# powerblade_3v1.net
KiCad netlist of a schematic drawn in EAGLE
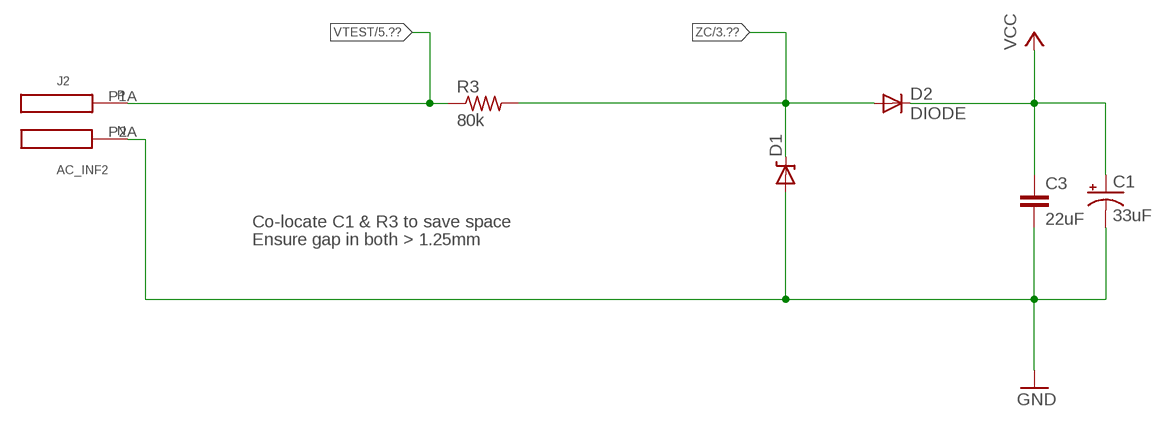
[diagram p0: schematic, sheet 1]
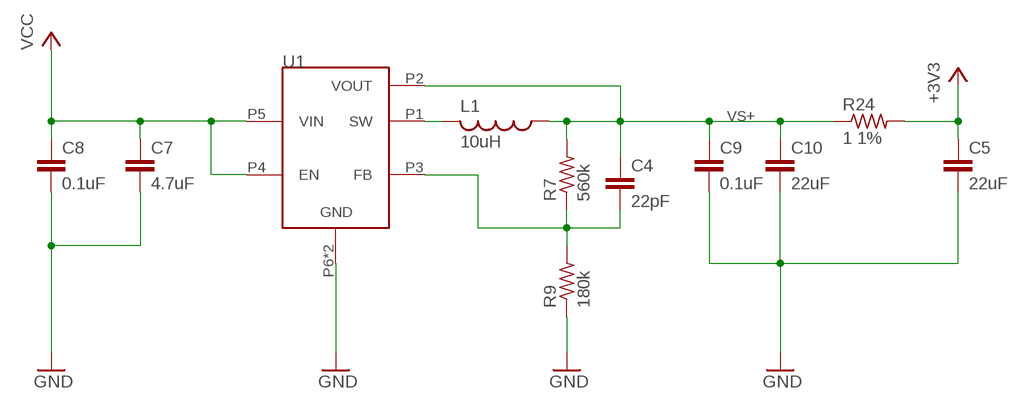
[diagram p1: schematic, sheet 2]
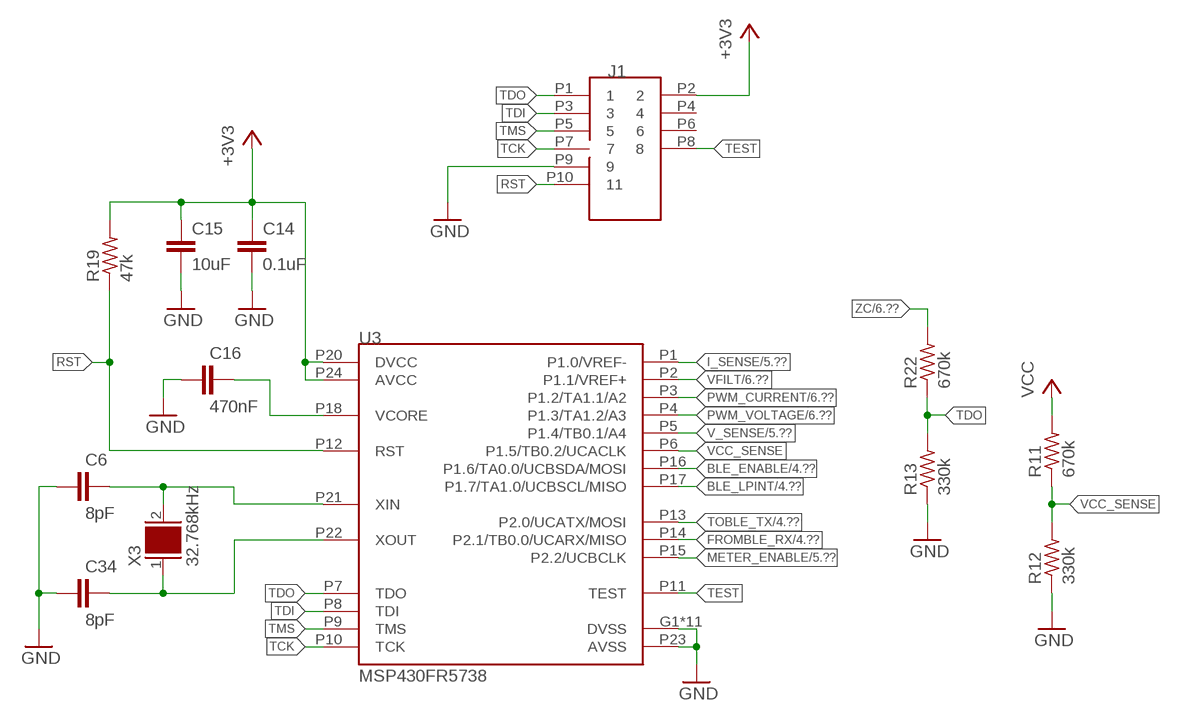
[diagram p2: schematic, sheet 3]
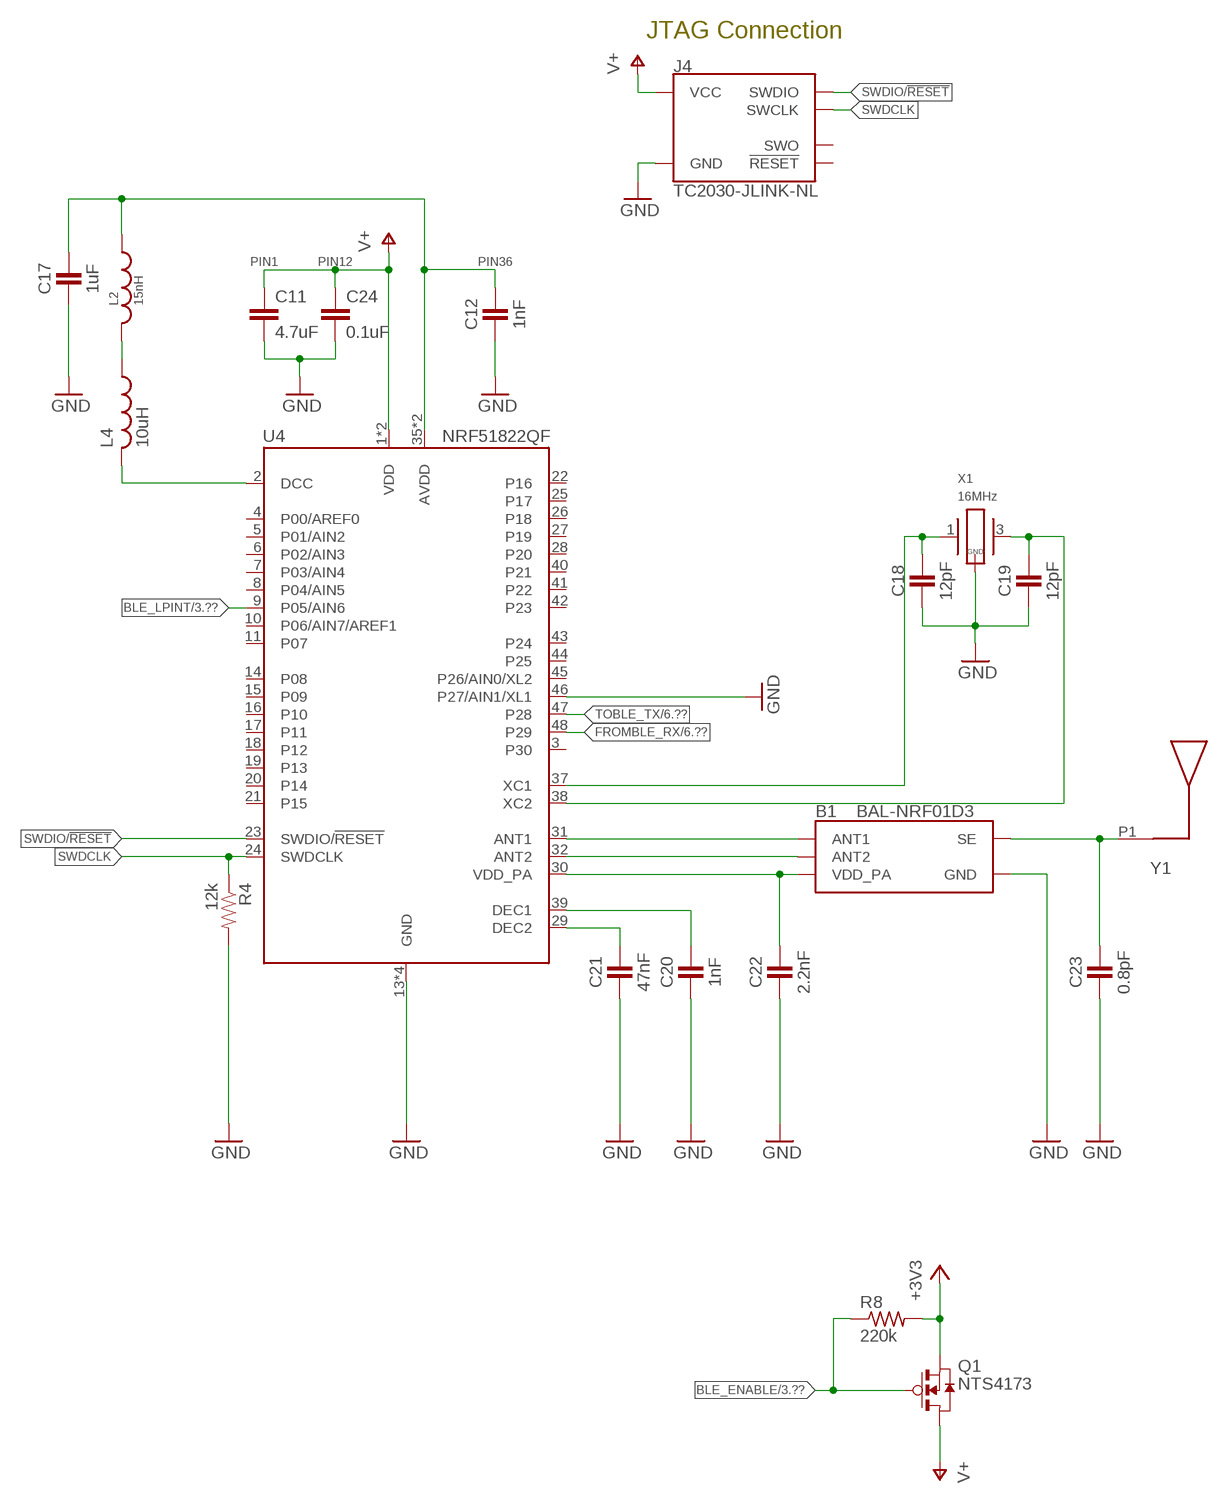
[diagram p3: schematic, sheet 4]
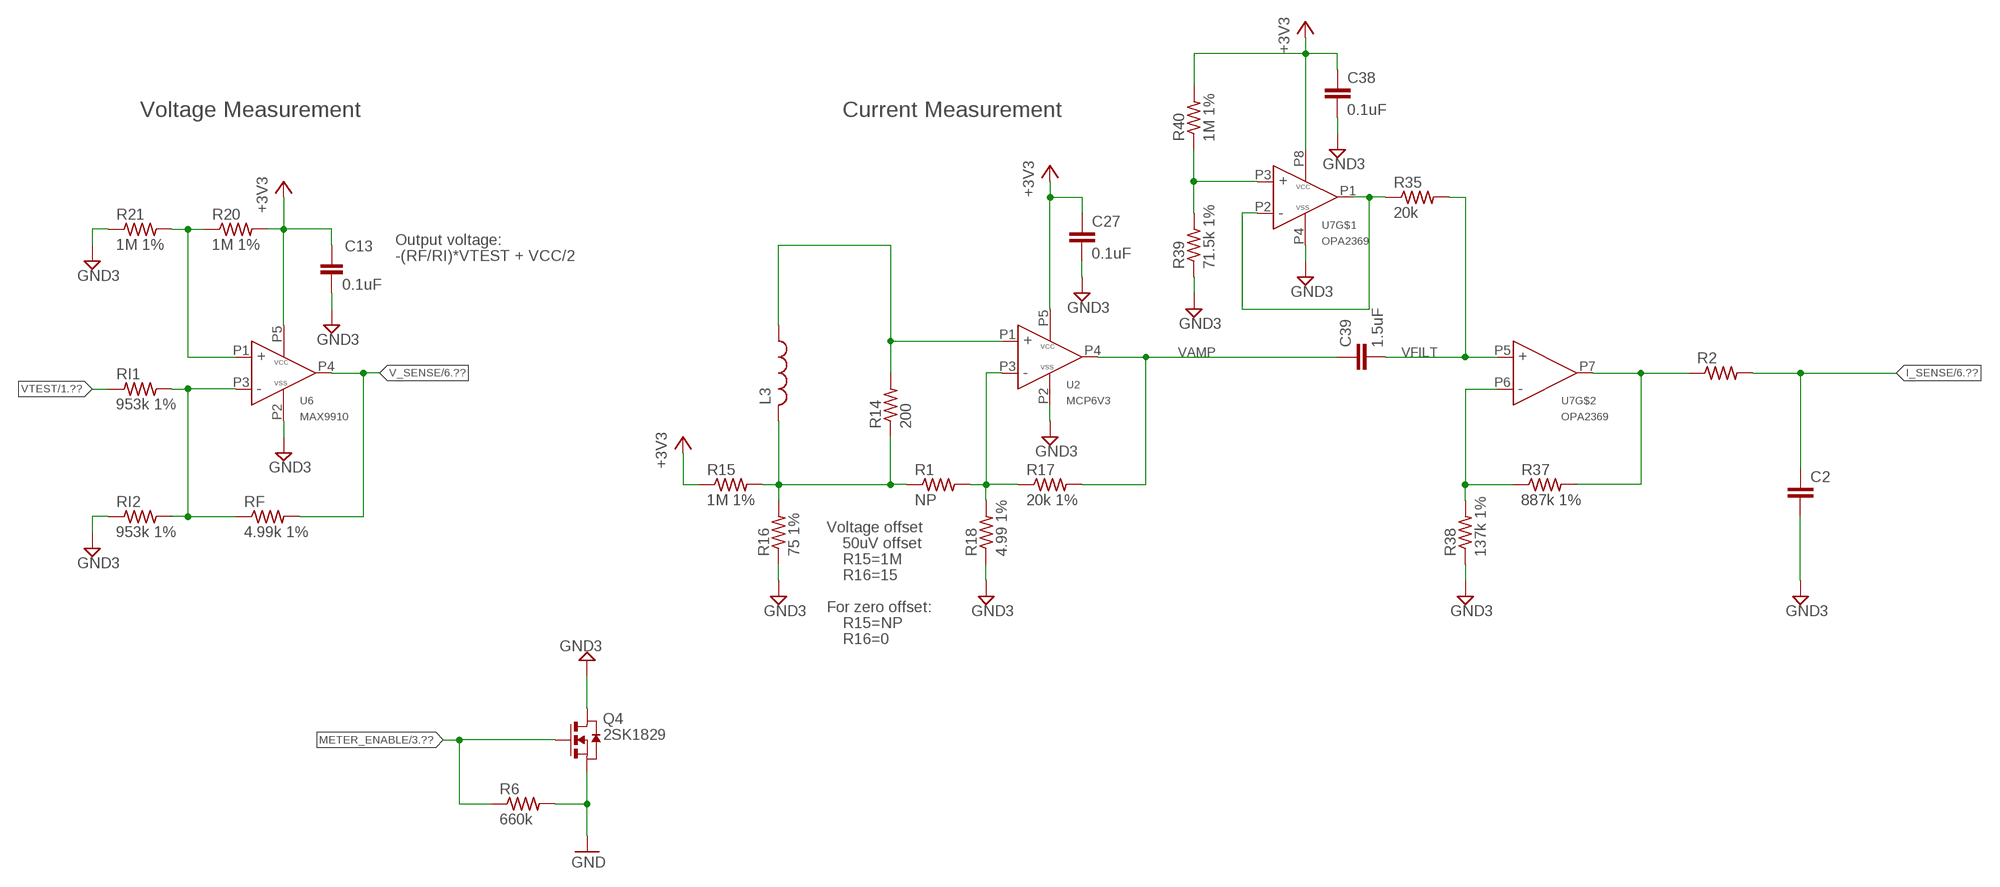
[diagram p4: schematic, sheet 5]
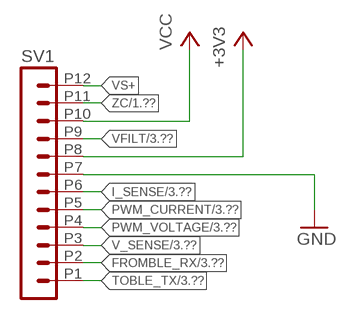
[diagram p5: schematic, sheet 6]

(export (version "E")
  (design (tool "Eeschema 10.0.6"))
  (components
    (comp (ref "C2")
      (value "C-EUC0402_SM")
      (footprint "eagle-import:C0402_SM")
      (libsource (lib "eagle-import") (part "C-EUC0402_SM"))
    )
    (comp (ref "C13")
      (value "0.1uF")
      (footprint "eagle-import:0402_CAP")
      (libsource (lib "eagle-import") (part "CAPACITOR"))
    )
    (comp (ref "C27")
      (value "0.1uF")
      (footprint "eagle-import:C0402_SM")
      (libsource (lib "eagle-import") (part "C-EUC0402_SM"))
    )
    (comp (ref "C38")
      (value "0.1uF")
      (footprint "eagle-import:C0402_SM")
      (libsource (lib "eagle-import") (part "C-EUC0402_SM"))
    )
    (comp (ref "C39")
      (value "1.5uF")
      (footprint "eagle-import:C0402_SM")
      (libsource (lib "eagle-import") (part "C-EUC0402_SM"))
    )
    (comp (ref "L3")
      (value "L-USL0805")
      (footprint "eagle-import:L0805")
      (libsource (lib "eagle-import") (part "L-USL0805"))
    )
    (comp (ref "Q4")
      (value "2SK1829")
      (footprint "eagle-import:SC-70-3")
      (libsource (lib "eagle-import") (part "2SK1829"))
    )
    (comp (ref "R1")
      (value "NP")
      (footprint "eagle-import:R0402_SM")
      (libsource (lib "eagle-import") (part "R-US_R0402_SM"))
    )
    (comp (ref "R2")
      (value "R-US_R0402_SM")
      (footprint "eagle-import:R0402_SM")
      (libsource (lib "eagle-import") (part "R-US_R0402_SM"))
    )
    (comp (ref "R6")
      (value "660k")
      (footprint "eagle-import:R0402_SM")
      (libsource (lib "eagle-import") (part "R-US_R0402_SM"))
    )
    (comp (ref "R14")
      (value "200")
      (footprint "eagle-import:R0402_SM")
      (libsource (lib "eagle-import") (part "R-US_R0402_SM"))
    )
    (comp (ref "R15")
      (value "1M 1%")
      (footprint "eagle-import:R0402_SM")
      (libsource (lib "eagle-import") (part "R-US_R0402_SM"))
    )
    (comp (ref "R16")
      (value "75 1%")
      (footprint "eagle-import:R0402_SM")
      (libsource (lib "eagle-import") (part "R-US_R0402_SM"))
    )
    (comp (ref "R17")
      (value "20k 1%")
      (footprint "eagle-import:R0402_SM")
      (libsource (lib "eagle-import") (part "R-US_R0402_SM"))
    )
    (comp (ref "R18")
      (value "4.99 1%")
      (footprint "eagle-import:R0402_SM")
      (libsource (lib "eagle-import") (part "R-US_R0402_SM"))
    )
    (comp (ref "R20")
      (value "1M 1%")
      (footprint "eagle-import:R0402_SM")
      (libsource (lib "eagle-import") (part "R-US_R0402_SM"))
    )
    (comp (ref "R21")
      (value "1M 1%")
      (footprint "eagle-import:R0402_SM")
      (libsource (lib "eagle-import") (part "R-US_R0402_SM"))
    )
    (comp (ref "R35")
      (value "20k")
      (footprint "eagle-import:R0402_SM")
      (libsource (lib "eagle-import") (part "R-US_R0402_SM"))
    )
    (comp (ref "R37")
      (value "887k 1%")
      (footprint "eagle-import:R0402_SM")
      (libsource (lib "eagle-import") (part "R-US_R0402_SM"))
    )
    (comp (ref "R38")
      (value "137k 1%")
      (footprint "eagle-import:R0402_SM")
      (libsource (lib "eagle-import") (part "R-US_R0402_SM"))
    )
    (comp (ref "R39")
      (value "71.5k 1%")
      (footprint "eagle-import:R0402_SM")
      (libsource (lib "eagle-import") (part "R-US_R0402_SM"))
    )
    (comp (ref "R40")
      (value "1M 1%")
      (footprint "eagle-import:R0402_SM")
      (libsource (lib "eagle-import") (part "R-US_R0402_SM"))
    )
    (comp (ref "RF")
      (value "4.99k 1%")
      (footprint "eagle-import:R0402_SM")
      (libsource (lib "eagle-import") (part "R-US_R0402_SM"))
    )
    (comp (ref "RI1")
      (value "953k 1%")
      (footprint "eagle-import:R0402_SM")
      (libsource (lib "eagle-import") (part "R-US_R0402_SM"))
    )
    (comp (ref "RI2")
      (value "953k 1%")
      (footprint "eagle-import:R0402_SM")
      (libsource (lib "eagle-import") (part "R-US_R0402_SM"))
    )
    (comp (ref "U2")
      (value "MCP6V3")
      (footprint "eagle-import:SC70-5")
      (libsource (lib "eagle-import") (part "MCP6V3"))
    )
    (comp (ref "U6")
      (value "MAX9910")
      (footprint "eagle-import:SC70-5")
      (fields (field (name "DIGIKEY") "296-25252-1-ND"))
      (libsource (lib "eagle-import") (part "MAX9910"))
    )
    (comp (ref "U7")
      (value "OPA2369")
      (footprint "eagle-import:SOT-23-8")
      (libsource (lib "eagle-import") (part "OPA2369"))
    )
    (comp (ref "C6")
      (value "8pF")
      (footprint "eagle-import:C0402_SM")
      (libsource (lib "eagle-import") (part "C-EUC0402_SM"))
    )
    (comp (ref "C14")
      (value "0.1uF")
      (footprint "eagle-import:C0402_SM")
      (libsource (lib "eagle-import") (part "C-EUC0402_SM"))
    )
    (comp (ref "C15")
      (value "10uF")
      (footprint "eagle-import:C0603_SM")
      (libsource (lib "eagle-import") (part "C-EUC0603_SM"))
    )
    (comp (ref "C16")
      (value "470nF")
      (footprint "eagle-import:C0402_SM")
      (libsource (lib "eagle-import") (part "C-EUC0402_SM"))
    )
    (comp (ref "C34")
      (value "8pF")
      (footprint "eagle-import:C0402_SM")
      (libsource (lib "eagle-import") (part "C-EUC0402_SM"))
    )
    (comp (ref "J1")
      (value "JTAG_14PIN_IDC-ND")
      (footprint "eagle-import:TC2050-IDC-NL-430-ND")
      (libsource (lib "eagle-import") (part "JTAG_14PIN_IDC-ND"))
    )
    (comp (ref "R11")
      (value "670k")
      (footprint "eagle-import:R0402_SM")
      (libsource (lib "eagle-import") (part "R-US_R0402_SM"))
    )
    (comp (ref "R12")
      (value "330k")
      (footprint "eagle-import:R0402_SM")
      (libsource (lib "eagle-import") (part "R-US_R0402_SM"))
    )
    (comp (ref "R13")
      (value "330k")
      (footprint "eagle-import:R0402_SM")
      (libsource (lib "eagle-import") (part "R-US_R0402_SM"))
    )
    (comp (ref "R19")
      (value "47k")
      (footprint "eagle-import:R0402_SM")
      (libsource (lib "eagle-import") (part "R-US_R0402_SM"))
    )
    (comp (ref "R22")
      (value "670k")
      (footprint "eagle-import:R0402_SM")
      (libsource (lib "eagle-import") (part "R-US_R0402_SM"))
    )
    (comp (ref "U3")
      (value "MSP430FR5738")
      (footprint "eagle-import:VQFN-24")
      (libsource (lib "eagle-import") (part "MSP430FR5738"))
    )
    (comp (ref "X3")
      (value "32.768kHz")
      (footprint "eagle-import:0805")
      (libsource (lib "eagle-import") (part "CRYSTAL_0805"))
    )
    (comp (ref "C4")
      (value "22pF")
      (footprint "eagle-import:C0402_SM")
      (libsource (lib "eagle-import") (part "C-EUC0402_SM"))
    )
    (comp (ref "C5")
      (value "22uF")
      (footprint "eagle-import:C0603_TN")
      (libsource (lib "eagle-import") (part "C-EUC0603_TN"))
    )
    (comp (ref "C7")
      (value "4.7uF")
      (footprint "eagle-import:C0402_SM")
      (libsource (lib "eagle-import") (part "C-EUC0402_SM"))
    )
    (comp (ref "C8")
      (value "0.1uF")
      (footprint "eagle-import:C0402_SM")
      (libsource (lib "eagle-import") (part "C-EUC0402_SM"))
    )
    (comp (ref "C9")
      (value "0.1uF")
      (footprint "eagle-import:C0402_SM")
      (libsource (lib "eagle-import") (part "C-EUC0402_SM"))
    )
    (comp (ref "C10")
      (value "22uF")
      (footprint "eagle-import:C0603_SM")
      (libsource (lib "eagle-import") (part "C-EUC0603_SM"))
    )
    (comp (ref "L1")
      (value "10uH")
      (footprint "eagle-import:L0805")
      (libsource (lib "eagle-import") (part "L-USL0805"))
    )
    (comp (ref "R7")
      (value "560k")
      (footprint "eagle-import:R0402_SM")
      (libsource (lib "eagle-import") (part "R-US_R0402_SM"))
    )
    (comp (ref "R9")
      (value "180k")
      (footprint "eagle-import:R0402_SM")
      (libsource (lib "eagle-import") (part "R-US_R0402_SM"))
    )
    (comp (ref "R24")
      (value "1 1%")
      (footprint "eagle-import:R0603_SM")
      (libsource (lib "eagle-import") (part "R-US_R0603_SM"))
    )
    (comp (ref "U1")
      (value "TPS62122")
      (footprint "eagle-import:WDFN-6")
      (libsource (lib "eagle-import") (part "TPS62122"))
    )
    (comp (ref "C1")
      (value "33uF")
      (footprint "eagle-import:CPOL0805_SM")
      (libsource (lib "eagle-import") (part "CPOL-US0805_SM"))
    )
    (comp (ref "C3")
      (value "22uF")
      (footprint "eagle-import:C0603_SM")
      (libsource (lib "eagle-import") (part "C-EUC0603_SM"))
    )
    (comp (ref "D1")
      (value "ZENERBZT52")
      (footprint "eagle-import:BZT52")
      (fields (field (name "DIGIKEY") "BZT52C10T-7DICT-ND "))
      (libsource (lib "eagle-import") (part "ZENERBZT52"))
    )
    (comp (ref "D2")
      (value "DIODE")
      (footprint "eagle-import:BAS521")
      (libsource (lib "eagle-import") (part "DIODE"))
    )
    (comp (ref "J2")
      (value "AC_INF2")
      (footprint "eagle-import:AC3_F2")
      (libsource (lib "eagle-import") (part "AC_INF2"))
    )
    (comp (ref "R3")
      (value "80k")
      (footprint "eagle-import:R1210")
      (libsource (lib "eagle-import") (part "R-US_R1210"))
    )
    (comp (ref "B1")
      (value "BAL-NRF01D3")
      (footprint "eagle-import:BAL-NRF01D3")
      (libsource (lib "eagle-import") (part "BAL-NRF01D3"))
    )
    (comp (ref "C11")
      (value "4.7uF")
      (footprint "eagle-import:C0402_SM")
      (libsource (lib "eagle-import") (part "C-EUC0402_SM"))
    )
    (comp (ref "C12")
      (value "1nF")
      (footprint "eagle-import:0402_CAP")
      (libsource (lib "eagle-import") (part "CAPACITOR"))
    )
    (comp (ref "C17")
      (value "1uF")
      (footprint "eagle-import:0402_CAP")
      (libsource (lib "eagle-import") (part "CAPACITOR"))
    )
    (comp (ref "C18")
      (value "12pF")
      (footprint "eagle-import:0402_CAP")
      (libsource (lib "eagle-import") (part "CAPACITOR"))
    )
    (comp (ref "C19")
      (value "12pF")
      (footprint "eagle-import:0402_CAP")
      (libsource (lib "eagle-import") (part "CAPACITOR"))
    )
    (comp (ref "C20")
      (value "1nF")
      (footprint "eagle-import:0402_CAP")
      (libsource (lib "eagle-import") (part "CAPACITOR"))
    )
    (comp (ref "C21")
      (value "47nF")
      (footprint "eagle-import:0402_CAP")
      (libsource (lib "eagle-import") (part "CAPACITOR"))
    )
    (comp (ref "C22")
      (value "2.2nF")
      (footprint "eagle-import:0402_CAP")
      (libsource (lib "eagle-import") (part "CAPACITOR"))
    )
    (comp (ref "C23")
      (value "0.8pF")
      (footprint "eagle-import:0402_CAP")
      (libsource (lib "eagle-import") (part "CAPACITOR"))
    )
    (comp (ref "C24")
      (value "0.1uF")
      (footprint "eagle-import:C0402_SM")
      (libsource (lib "eagle-import") (part "C-EUC0402_SM"))
    )
    (comp (ref "J4")
      (value "TC2030-JLINK-NL")
      (footprint "eagle-import:TC2030-IDC-NL")
      (libsource (lib "eagle-import") (part "TC2030-JLINK-NL"))
    )
    (comp (ref "L2")
      (value "15nH")
      (footprint "eagle-import:0402_CAP")
      (libsource (lib "eagle-import") (part "INDUCTOR0402"))
    )
    (comp (ref "L4")
      (value "10uH")
      (footprint "eagle-import:C0603_TN")
      (libsource (lib "eagle-import") (part "L-USL0603_TN"))
    )
    (comp (ref "Q1")
      (value "NTS4173")
      (footprint "eagle-import:SC-70-3")
      (libsource (lib "eagle-import") (part "NTS4173"))
    )
    (comp (ref "R4")
      (value "12k")
      (footprint "eagle-import:0402_RES")
      (libsource (lib "eagle-import") (part "RESISTOR"))
    )
    (comp (ref "R8")
      (value "220k")
      (footprint "eagle-import:R0402_SM")
      (libsource (lib "eagle-import") (part "R-US_R0402_SM"))
    )
    (comp (ref "U4")
      (value "NRF51822QF")
      (footprint "eagle-import:QFN-48-6MM")
      (libsource (lib "eagle-import") (part "NRF51822QF"))
    )
    (comp (ref "X1")
      (value "16MHz")
      (footprint "eagle-import:TXC-8Y")
      (libsource (lib "eagle-import") (part "TXC-8Y"))
    )
    (comp (ref "Y1")
      (value "UREACH_XTEND")
      (footprint "eagle-import:UREACH_XTEND")
      (libsource (lib "eagle-import") (part "UREACH_XTEND"))
    )
    (comp (ref "SV1")
      (value "MA12-11M27")
      (footprint "eagle-import:MA12-1_1MM27")
      (libsource (lib "eagle-import") (part "MA12-11M27"))
    )
  )
  (nets
    (net (code "1") (name "+3V3") (class "Default")
      (node (ref "C13") (pin "1") (pinfunction "1_1") (pintype "bidirectional"))
      (node (ref "C14") (pin "1") (pinfunction "1_1") (pintype "passive"))
      (node (ref "C15") (pin "1") (pinfunction "1_1") (pintype "passive"))
      (node (ref "C27") (pin "1") (pinfunction "1_1") (pintype "passive"))
      (node (ref "C38") (pin "1") (pinfunction "1_1") (pintype "passive"))
      (node (ref "C5") (pin "1") (pinfunction "1_1") (pintype "passive"))
      (node (ref "J1") (pin "P2") (pinfunction "2_P2") (pintype "bidirectional"))
      (node (ref "Q1") (pin "P2") (pinfunction "S_P2") (pintype "passive"))
      (node (ref "R15") (pin "1") (pinfunction "1_1") (pintype "passive"))
      (node (ref "R19") (pin "2") (pinfunction "2_2") (pintype "passive"))
      (node (ref "R20") (pin "2") (pinfunction "2_2") (pintype "passive"))
      (node (ref "R24") (pin "2") (pinfunction "2_2") (pintype "passive"))
      (node (ref "R40") (pin "2") (pinfunction "2_2") (pintype "passive"))
      (node (ref "R8") (pin "2") (pinfunction "2_2") (pintype "passive"))
      (node (ref "SV1") (pin "P8") (pinfunction "8_P8") (pintype "passive"))
      (node (ref "U2") (pin "P5") (pinfunction "VCC_P5") (pintype "bidirectional"))
      (node (ref "U3") (pin "P20") (pinfunction "DVCC_P20") (pintype "bidirectional"))
      (node (ref "U3") (pin "P24") (pinfunction "AVCC_P24") (pintype "bidirectional"))
      (node (ref "U6") (pin "P5") (pinfunction "VCC_P5") (pintype "bidirectional"))
      (node (ref "U7") (pin "P8") (pinfunction "VCC_P8") (pintype "bidirectional"))
    )
    (net (code "2") (name "BLE_ENABLE") (class "Default")
      (node (ref "Q1") (pin "P1") (pinfunction "G_P1") (pintype "passive"))
      (node (ref "R8") (pin "1") (pinfunction "1_1") (pintype "passive"))
      (node (ref "U3") (pin "P16") (pinfunction "P1.6/TA0.0/UCBSDA/MOSI_P16") (pintype "bidirectional"))
    )
    (net (code "3") (name "BLE_LPINT") (class "Default")
      (node (ref "U3") (pin "P17") (pinfunction "P1.7/TA1.0/UCBSCL/MISO_P17") (pintype "bidirectional"))
      (node (ref "U4") (pin "9") (pinfunction "P05/AIN6_9") (pintype "bidirectional"))
    )
    (net (code "4") (name "FROMBLE_RX") (class "Default")
      (node (ref "SV1") (pin "P2") (pinfunction "2_P2") (pintype "passive"))
      (node (ref "U3") (pin "P14") (pinfunction "P2.1/TB0.0/UCARX/MISO_P14") (pintype "bidirectional"))
      (node (ref "U4") (pin "48") (pinfunction "P29_48") (pintype "bidirectional"))
    )
    (net (code "5") (name "GND") (class "Default")
      (node (ref "B1") (pin "GND") (pinfunction "GND_GND") (pintype "bidirectional"))
      (node (ref "C1") (pin "-") (pinfunction "-_-") (pintype "passive"))
      (node (ref "C10") (pin "2") (pinfunction "2_2") (pintype "passive"))
      (node (ref "C11") (pin "2") (pinfunction "2_2") (pintype "passive"))
      (node (ref "C12") (pin "2") (pinfunction "2_2") (pintype "bidirectional"))
      (node (ref "C14") (pin "2") (pinfunction "2_2") (pintype "passive"))
      (node (ref "C15") (pin "2") (pinfunction "2_2") (pintype "passive"))
      (node (ref "C16") (pin "1") (pinfunction "1_1") (pintype "passive"))
      (node (ref "C17") (pin "2") (pinfunction "2_2") (pintype "bidirectional"))
      (node (ref "C18") (pin "2") (pinfunction "2_2") (pintype "bidirectional"))
      (node (ref "C19") (pin "2") (pinfunction "2_2") (pintype "bidirectional"))
      (node (ref "C20") (pin "2") (pinfunction "2_2") (pintype "bidirectional"))
      (node (ref "C21") (pin "2") (pinfunction "2_2") (pintype "bidirectional"))
      (node (ref "C22") (pin "2") (pinfunction "2_2") (pintype "bidirectional"))
      (node (ref "C23") (pin "2") (pinfunction "2_2") (pintype "bidirectional"))
      (node (ref "C24") (pin "2") (pinfunction "2_2") (pintype "passive"))
      (node (ref "C3") (pin "2") (pinfunction "2_2") (pintype "passive"))
      (node (ref "C34") (pin "1") (pinfunction "1_1") (pintype "passive"))
      (node (ref "C5") (pin "2") (pinfunction "2_2") (pintype "passive"))
      (node (ref "C6") (pin "1") (pinfunction "1_1") (pintype "passive"))
      (node (ref "C7") (pin "2") (pinfunction "2_2") (pintype "passive"))
      (node (ref "C8") (pin "2") (pinfunction "2_2") (pintype "passive"))
      (node (ref "C9") (pin "2") (pinfunction "2_2") (pintype "passive"))
      (node (ref "D1") (pin "A") (pinfunction "A_A") (pintype "passive"))
      (node (ref "J1") (pin "P9") (pinfunction "9_P9") (pintype "bidirectional"))
      (node (ref "J2") (pin "P2A") (pinfunction "N_P2A") (pintype "bidirectional"))
      (node (ref "J4") (pin "5") (pinfunction "GND_5") (pintype "bidirectional"))
      (node (ref "Q4") (pin "P2") (pinfunction "S_P2") (pintype "passive"))
      (node (ref "R12") (pin "1") (pinfunction "1_1") (pintype "passive"))
      (node (ref "R13") (pin "1") (pinfunction "1_1") (pintype "passive"))
      (node (ref "R4") (pin "2") (pinfunction "2_2") (pintype "passive"))
      (node (ref "R6") (pin "2") (pinfunction "2_2") (pintype "passive"))
      (node (ref "R9") (pin "1") (pinfunction "1_1") (pintype "passive"))
      (node (ref "SV1") (pin "P7") (pinfunction "7_P7") (pintype "passive"))
      (node (ref "U1") (pin "P6") (pinfunction "GND_P6") (pintype "bidirectional"))
      (node (ref "U1") (pin "PAD") (pinfunction "GND_PAD") (pintype "bidirectional"))
      (node (ref "U3") (pin "G1") (pinfunction "DVSS_G1") (pintype "bidirectional"))
      (node (ref "U3") (pin "G2") (pinfunction "DVSS_G2") (pintype "bidirectional"))
      (node (ref "U3") (pin "G3") (pinfunction "DVSS_G3") (pintype "bidirectional"))
      (node (ref "U3") (pin "G4") (pinfunction "DVSS_G4") (pintype "bidirectional"))
      (node (ref "U3") (pin "G5") (pinfunction "DVSS_G5") (pintype "bidirectional"))
      (node (ref "U3") (pin "G6") (pinfunction "DVSS_G6") (pintype "bidirectional"))
      (node (ref "U3") (pin "G7") (pinfunction "DVSS_G7") (pintype "bidirectional"))
      (node (ref "U3") (pin "G8") (pinfunction "DVSS_G8") (pintype "bidirectional"))
      (node (ref "U3") (pin "G9") (pinfunction "DVSS_G9") (pintype "bidirectional"))
      (node (ref "U3") (pin "P19") (pinfunction "DVSS_P19") (pintype "bidirectional"))
      (node (ref "U3") (pin "P23") (pinfunction "AVSS_P23") (pintype "bidirectional"))
      (node (ref "U3") (pin "PAD") (pinfunction "DVSS_PAD") (pintype "bidirectional"))
      (node (ref "U4") (pin "13") (pinfunction "GND_13") (pintype "bidirectional"))
      (node (ref "U4") (pin "33") (pinfunction "GND_33") (pintype "bidirectional"))
      (node (ref "U4") (pin "34") (pinfunction "GND_34") (pintype "bidirectional"))
      (node (ref "U4") (pin "46") (pinfunction "P27/AIN1/XL1_46") (pintype "bidirectional"))
      (node (ref "U4") (pin "GND") (pinfunction "GND_GND") (pintype "bidirectional"))
      (node (ref "X1") (pin "2") (pinfunction "GND_2") (pintype "bidirectional"))
      (node (ref "X1") (pin "4") (pinfunction "GND_4") (pintype "bidirectional"))
    )
    (net (code "6") (name "GND3") (class "Default")
      (node (ref "C13") (pin "2") (pinfunction "2_2") (pintype "bidirectional"))
      (node (ref "C2") (pin "2") (pinfunction "2_2") (pintype "passive"))
      (node (ref "C27") (pin "2") (pinfunction "2_2") (pintype "passive"))
      (node (ref "C38") (pin "2") (pinfunction "2_2") (pintype "passive"))
      (node (ref "Q4") (pin "P3") (pinfunction "D_P3") (pintype "passive"))
      (node (ref "R16") (pin "1") (pinfunction "1_1") (pintype "passive"))
      (node (ref "R18") (pin "1") (pinfunction "1_1") (pintype "passive"))
      (node (ref "R21") (pin "1") (pinfunction "1_1") (pintype "passive"))
      (node (ref "R38") (pin "1") (pinfunction "1_1") (pintype "passive"))
      (node (ref "R39") (pin "1") (pinfunction "1_1") (pintype "passive"))
      (node (ref "RI2") (pin "1") (pinfunction "1_1") (pintype "passive"))
      (node (ref "U2") (pin "P2") (pinfunction "VSS_P2") (pintype "bidirectional"))
      (node (ref "U6") (pin "P2") (pinfunction "VSS_P2") (pintype "bidirectional"))
      (node (ref "U7") (pin "P4") (pinfunction "VSS_P4") (pintype "bidirectional"))
    )
    (net (code "7") (name "I_SENSE") (class "Default")
      (node (ref "C2") (pin "1") (pinfunction "1_1") (pintype "passive"))
      (node (ref "R2") (pin "2") (pinfunction "2_2") (pintype "passive"))
      (node (ref "SV1") (pin "P6") (pinfunction "6_P6") (pintype "passive"))
      (node (ref "U3") (pin "P1") (pinfunction "P1.0/VREF-_P1") (pintype "bidirectional"))
    )
    (net (code "8") (name "METER_ENABLE") (class "Default")
      (node (ref "Q4") (pin "P1") (pinfunction "G_P1") (pintype "passive"))
      (node (ref "R6") (pin "1") (pinfunction "1_1") (pintype "passive"))
      (node (ref "U3") (pin "P15") (pinfunction "P2.2/UCBCLK_P15") (pintype "bidirectional"))
    )
    (net (code "9") (name "Net-(B1-PadSE)") (class "Default")
      (node (ref "B1") (pin "SE") (pinfunction "SE_SE") (pintype "bidirectional"))
      (node (ref "C23") (pin "1") (pinfunction "1_1") (pintype "bidirectional"))
      (node (ref "Y1") (pin "P1") (pinfunction "P1_P1") (pintype "bidirectional"))
    )
    (net (code "10") (name "Net-(B1-VDD_PA)") (class "Default")
      (node (ref "B1") (pin "VCC") (pinfunction "VDD_PA_VCC") (pintype "bidirectional"))
      (node (ref "C22") (pin "1") (pinfunction "1_1") (pintype "bidirectional"))
      (node (ref "U4") (pin "30") (pinfunction "VDD_PA_30") (pintype "bidirectional"))
    )
    (net (code "11") (name "Net-(C12-Pad1)") (class "Default")
      (node (ref "C12") (pin "1") (pinfunction "1_1") (pintype "bidirectional"))
      (node (ref "C17") (pin "1") (pinfunction "1_1") (pintype "bidirectional"))
      (node (ref "L2") (pin "1") (pinfunction "1_1") (pintype "bidirectional"))
      (node (ref "U4") (pin "35") (pinfunction "AVDD_35") (pintype "bidirectional"))
      (node (ref "U4") (pin "36") (pinfunction "AVDD_36") (pintype "bidirectional"))
    )
    (net (code "12") (name "Net-(L2-Pad2)") (class "Default")
      (node (ref "L2") (pin "2") (pinfunction "2_2") (pintype "bidirectional"))
      (node (ref "L4") (pin "1") (pinfunction "1_1") (pintype "passive"))
    )
    (net (code "13") (name "Net-(L3-Pad2)") (class "Default")
      (node (ref "L3") (pin "2") (pinfunction "2_2") (pintype "passive"))
      (node (ref "R1") (pin "1") (pinfunction "1_1") (pintype "passive"))
      (node (ref "R14") (pin "1") (pinfunction "1_1") (pintype "passive"))
      (node (ref "R15") (pin "2") (pinfunction "2_2") (pintype "passive"))
      (node (ref "R16") (pin "2") (pinfunction "2_2") (pintype "passive"))
    )
    (net (code "14") (name "Net-(U1-FB)") (class "Default")
      (node (ref "C4") (pin "2") (pinfunction "2_2") (pintype "passive"))
      (node (ref "R7") (pin "1") (pinfunction "1_1") (pintype "passive"))
      (node (ref "R9") (pin "2") (pinfunction "2_2") (pintype "passive"))
      (node (ref "U1") (pin "P3") (pinfunction "FB_P3") (pintype "bidirectional"))
    )
    (net (code "15") (name "Net-(U1-SW)") (class "Default")
      (node (ref "L1") (pin "2") (pinfunction "2_2") (pintype "passive"))
      (node (ref "U1") (pin "P1") (pinfunction "SW_P1") (pintype "bidirectional"))
    )
    (net (code "16") (name "Net-(U2-IN+)") (class "Default")
      (node (ref "L3") (pin "1") (pinfunction "1_1") (pintype "passive"))
      (node (ref "R14") (pin "2") (pinfunction "2_2") (pintype "passive"))
      (node (ref "U2") (pin "P1") (pinfunction "IN+_P1") (pintype "bidirectional"))
    )
    (net (code "17") (name "Net-(U2-IN-)") (class "Default")
      (node (ref "R1") (pin "2") (pinfunction "2_2") (pintype "passive"))
      (node (ref "R17") (pin "1") (pinfunction "1_1") (pintype "passive"))
      (node (ref "R18") (pin "2") (pinfunction "2_2") (pintype "passive"))
      (node (ref "U2") (pin "P3") (pinfunction "IN-_P3") (pintype "bidirectional"))
    )
    (net (code "18") (name "Net-(U3-VCORE)") (class "Default")
      (node (ref "C16") (pin "2") (pinfunction "2_2") (pintype "passive"))
      (node (ref "U3") (pin "P18") (pinfunction "VCORE_P18") (pintype "bidirectional"))
    )
    (net (code "19") (name "Net-(U3-XIN)") (class "Default")
      (node (ref "C6") (pin "2") (pinfunction "2_2") (pintype "passive"))
      (node (ref "U3") (pin "P21") (pinfunction "XIN_P21") (pintype "bidirectional"))
      (node (ref "X3") (pin "2") (pinfunction "P2_2") (pintype "bidirectional"))
    )
    (net (code "20") (name "Net-(U3-XOUT)") (class "Default")
      (node (ref "C34") (pin "2") (pinfunction "2_2") (pintype "passive"))
      (node (ref "U3") (pin "P22") (pinfunction "XOUT_P22") (pintype "bidirectional"))
      (node (ref "X3") (pin "1") (pinfunction "P1_1") (pintype "bidirectional"))
    )
    (net (code "21") (name "Net-(U4-ANT1)") (class "Default")
      (node (ref "B1") (pin "ANT1") (pinfunction "ANT1_ANT1") (pintype "bidirectional"))
      (node (ref "U4") (pin "31") (pinfunction "ANT1_31") (pintype "bidirectional"))
    )
    (net (code "22") (name "Net-(U4-ANT2)") (class "Default")
      (node (ref "B1") (pin "ANT2") (pinfunction "ANT2_ANT2") (pintype "bidirectional"))
      (node (ref "U4") (pin "32") (pinfunction "ANT2_32") (pintype "bidirectional"))
    )
    (net (code "23") (name "Net-(U4-DCC)") (class "Default")
      (node (ref "L4") (pin "2") (pinfunction "2_2") (pintype "passive"))
      (node (ref "U4") (pin "2") (pinfunction "DCC_2") (pintype "bidirectional"))
    )
    (net (code "24") (name "Net-(U4-DEC1)") (class "Default")
      (node (ref "C20") (pin "1") (pinfunction "1_1") (pintype "bidirectional"))
      (node (ref "U4") (pin "39") (pinfunction "DEC1_39") (pintype "bidirectional"))
    )
    (net (code "25") (name "Net-(U4-DEC2)") (class "Default")
      (node (ref "C21") (pin "1") (pinfunction "1_1") (pintype "bidirectional"))
      (node (ref "U4") (pin "29") (pinfunction "DEC2_29") (pintype "bidirectional"))
    )
    (net (code "26") (name "Net-(U4-XC1)") (class "Default")
      (node (ref "C18") (pin "1") (pinfunction "1_1") (pintype "bidirectional"))
      (node (ref "U4") (pin "37") (pinfunction "XC1_37") (pintype "bidirectional"))
      (node (ref "X1") (pin "1") (pinfunction "1_1") (pintype "bidirectional"))
    )
    (net (code "27") (name "Net-(U4-XC2)") (class "Default")
      (node (ref "C19") (pin "1") (pinfunction "1_1") (pintype "bidirectional"))
      (node (ref "U4") (pin "38") (pinfunction "XC2_38") (pintype "bidirectional"))
      (node (ref "X1") (pin "3") (pinfunction "2_3") (pintype "bidirectional"))
    )
    (net (code "28") (name "Net-(U6-IN+)") (class "Default")
      (node (ref "R20") (pin "1") (pinfunction "1_1") (pintype "passive"))
      (node (ref "R21") (pin "2") (pinfunction "2_2") (pintype "passive"))
      (node (ref "U6") (pin "P1") (pinfunction "IN+_P1") (pintype "bidirectional"))
    )
    (net (code "29") (name "Net-(U6-IN-)") (class "Default")
      (node (ref "RF") (pin "1") (pinfunction "1_1") (pintype "passive"))
      (node (ref "RI1") (pin "2") (pinfunction "2_2") (pintype "passive"))
      (node (ref "RI2") (pin "2") (pinfunction "2_2") (pintype "passive"))
      (node (ref "U6") (pin "P3") (pinfunction "IN-_P3") (pintype "bidirectional"))
    )
    (net (code "30") (name "Net-(U7A-IN+)") (class "Default")
      (node (ref "R39") (pin "2") (pinfunction "2_2") (pintype "passive"))
      (node (ref "R40") (pin "1") (pinfunction "1_1") (pintype "passive"))
      (node (ref "U7") (pin "P3") (pinfunction "IN+_P3") (pintype "bidirectional"))
    )
    (net (code "31") (name "Net-(U7A-IN-)") (class "Default")
      (node (ref "R35") (pin "1") (pinfunction "1_1") (pintype "passive"))
      (node (ref "U7") (pin "P1") (pinfunction "OUT_P1") (pintype "bidirectional"))
      (node (ref "U7") (pin "P2") (pinfunction "IN-_P2") (pintype "bidirectional"))
    )
    (net (code "32") (name "Net-(U7B-IN-)") (class "Default")
      (node (ref "R37") (pin "1") (pinfunction "1_1") (pintype "passive"))
      (node (ref "R38") (pin "2") (pinfunction "2_2") (pintype "passive"))
      (node (ref "U7") (pin "P6") (pinfunction "IN-_P6") (pintype "bidirectional"))
    )
    (net (code "33") (name "Net-(U7B-OUT)") (class "Default")
      (node (ref "R2") (pin "1") (pinfunction "1_1") (pintype "passive"))
      (node (ref "R37") (pin "2") (pinfunction "2_2") (pintype "passive"))
      (node (ref "U7") (pin "P7") (pinfunction "OUT_P7") (pintype "bidirectional"))
    )
    (net (code "34") (name "PWM_CURRENT") (class "Default")
      (node (ref "SV1") (pin "P5") (pinfunction "5_P5") (pintype "passive"))
      (node (ref "U3") (pin "P3") (pinfunction "P1.2/TA1.1/A2_P3") (pintype "bidirectional"))
    )
    (net (code "35") (name "PWM_VOLTAGE") (class "Default")
      (node (ref "SV1") (pin "P4") (pinfunction "4_P4") (pintype "passive"))
      (node (ref "U3") (pin "P4") (pinfunction "P1.3/TA1.2/A3_P4") (pintype "bidirectional"))
    )
    (net (code "36") (name "RST") (class "Default")
      (node (ref "J1") (pin "P10") (pinfunction "11_P10") (pintype "bidirectional"))
      (node (ref "R19") (pin "1") (pinfunction "1_1") (pintype "passive"))
      (node (ref "U3") (pin "P12") (pinfunction "RST_P12") (pintype "bidirectional"))
    )
    (net (code "37") (name "SWDCLK") (class "Default")
      (node (ref "J4") (pin "4") (pinfunction "SWCLK_4") (pintype "bidirectional"))
      (node (ref "R4") (pin "1") (pinfunction "1_1") (pintype "passive"))
      (node (ref "U4") (pin "24") (pinfunction "SWDCLK_24") (pintype "bidirectional"))
    )
    (net (code "38") (name "SWDIO{slash}~{RESET}") (class "Default")
      (node (ref "J4") (pin "2") (pinfunction "SWDIO_2") (pintype "bidirectional"))
      (node (ref "U4") (pin "23") (pinfunction "SWDIO/~{RESET}_23") (pintype "bidirectional"))
    )
    (net (code "39") (name "TCK") (class "Default")
      (node (ref "J1") (pin "P7") (pinfunction "7_P7") (pintype "bidirectional"))
      (node (ref "U3") (pin "P10") (pinfunction "TCK_P10") (pintype "bidirectional"))
    )
    (net (code "40") (name "TDI") (class "Default")
      (node (ref "J1") (pin "P3") (pinfunction "3_P3") (pintype "bidirectional"))
      (node (ref "U3") (pin "P8") (pinfunction "TDI_P8") (pintype "bidirectional"))
    )
    (net (code "41") (name "TDO") (class "Default")
      (node (ref "J1") (pin "P1") (pinfunction "1_P1") (pintype "bidirectional"))
      (node (ref "R13") (pin "2") (pinfunction "2_2") (pintype "passive"))
      (node (ref "R22") (pin "1") (pinfunction "1_1") (pintype "passive"))
      (node (ref "U3") (pin "P7") (pinfunction "TDO_P7") (pintype "bidirectional"))
    )
    (net (code "42") (name "TEST") (class "Default")
      (node (ref "J1") (pin "P8") (pinfunction "8_P8") (pintype "bidirectional"))
      (node (ref "U3") (pin "P11") (pinfunction "TEST_P11") (pintype "bidirectional"))
    )
    (net (code "43") (name "TMS") (class "Default")
      (node (ref "J1") (pin "P5") (pinfunction "5_P5") (pintype "bidirectional"))
      (node (ref "U3") (pin "P9") (pinfunction "TMS_P9") (pintype "bidirectional"))
    )
    (net (code "44") (name "TOBLE_TX") (class "Default")
      (node (ref "SV1") (pin "P1") (pinfunction "1_P1") (pintype "passive"))
      (node (ref "U3") (pin "P13") (pinfunction "P2.0/UCATX/MOSI_P13") (pintype "bidirectional"))
      (node (ref "U4") (pin "47") (pinfunction "P28_47") (pintype "bidirectional"))
    )
    (net (code "45") (name "V+") (class "Default")
      (node (ref "C11") (pin "1") (pinfunction "1_1") (pintype "passive"))
      (node (ref "C24") (pin "1") (pinfunction "1_1") (pintype "passive"))
      (node (ref "J4") (pin "1") (pinfunction "VCC_1") (pintype "bidirectional"))
      (node (ref "Q1") (pin "P3") (pinfunction "D_P3") (pintype "passive"))
      (node (ref "U4") (pin "1") (pinfunction "VDD_1") (pintype "bidirectional"))
      (node (ref "U4") (pin "12") (pinfunction "VDD_12") (pintype "bidirectional"))
    )
    (net (code "46") (name "VAMP") (class "Default")
      (node (ref "C39") (pin "1") (pinfunction "1_1") (pintype "passive"))
      (node (ref "R17") (pin "2") (pinfunction "2_2") (pintype "passive"))
      (node (ref "U2") (pin "P4") (pinfunction "OUT_P4") (pintype "bidirectional"))
    )
    (net (code "47") (name "VCC") (class "Default")
      (node (ref "C1") (pin "+") (pinfunction "+_+") (pintype "passive"))
      (node (ref "C3") (pin "1") (pinfunction "1_1") (pintype "passive"))
      (node (ref "C7") (pin "1") (pinfunction "1_1") (pintype "passive"))
      (node (ref "C8") (pin "1") (pinfunction "1_1") (pintype "passive"))
      (node (ref "D2") (pin "C") (pinfunction "C_C") (pintype "passive"))
      (node (ref "R11") (pin "2") (pinfunction "2_2") (pintype "passive"))
      (node (ref "SV1") (pin "P10") (pinfunction "10_P10") (pintype "passive"))
      (node (ref "U1") (pin "P4") (pinfunction "EN_P4") (pintype "bidirectional"))
      (node (ref "U1") (pin "P5") (pinfunction "VIN_P5") (pintype "bidirectional"))
    )
    (net (code "48") (name "VCC_SENSE") (class "Default")
      (node (ref "R11") (pin "1") (pinfunction "1_1") (pintype "passive"))
      (node (ref "R12") (pin "2") (pinfunction "2_2") (pintype "passive"))
      (node (ref "U3") (pin "P6") (pinfunction "P1.5/TB0.2/UCACLK_P6") (pintype "bidirectional"))
    )
    (net (code "49") (name "VFILT") (class "Default")
      (node (ref "C39") (pin "2") (pinfunction "2_2") (pintype "passive"))
      (node (ref "R35") (pin "2") (pinfunction "2_2") (pintype "passive"))
      (node (ref "SV1") (pin "P9") (pinfunction "9_P9") (pintype "passive"))
      (node (ref "U3") (pin "P2") (pinfunction "P1.1/VREF+_P2") (pintype "bidirectional"))
      (node (ref "U7") (pin "P5") (pinfunction "IN+_P5") (pintype "bidirectional"))
    )
    (net (code "50") (name "VS+") (class "Default")
      (node (ref "C10") (pin "1") (pinfunction "1_1") (pintype "passive"))
      (node (ref "C4") (pin "1") (pinfunction "1_1") (pintype "passive"))
      (node (ref "C9") (pin "1") (pinfunction "1_1") (pintype "passive"))
      (node (ref "L1") (pin "1") (pinfunction "1_1") (pintype "passive"))
      (node (ref "R24") (pin "1") (pinfunction "1_1") (pintype "passive"))
      (node (ref "R7") (pin "2") (pinfunction "2_2") (pintype "passive"))
      (node (ref "SV1") (pin "P12") (pinfunction "12_P12") (pintype "passive"))
      (node (ref "U1") (pin "P2") (pinfunction "VOUT_P2") (pintype "bidirectional"))
    )
    (net (code "51") (name "VTEST") (class "Default")
      (node (ref "J2") (pin "P1A") (pinfunction "P_P1A") (pintype "bidirectional"))
      (node (ref "R3") (pin "1") (pinfunction "1_1") (pintype "passive"))
      (node (ref "RI1") (pin "1") (pinfunction "1_1") (pintype "passive"))
    )
    (net (code "52") (name "V_SENSE") (class "Default")
      (node (ref "RF") (pin "2") (pinfunction "2_2") (pintype "passive"))
      (node (ref "SV1") (pin "P3") (pinfunction "3_P3") (pintype "passive"))
      (node (ref "U3") (pin "P5") (pinfunction "P1.4/TB0.1/A4_P5") (pintype "bidirectional"))
      (node (ref "U6") (pin "P4") (pinfunction "OUT_P4") (pintype "bidirectional"))
    )
    (net (code "53") (name "ZC") (class "Default")
      (node (ref "D1") (pin "C") (pinfunction "C_C") (pintype "passive"))
      (node (ref "D2") (pin "A") (pinfunction "A_A") (pintype "passive"))
      (node (ref "R22") (pin "2") (pinfunction "2_2") (pintype "passive"))
      (node (ref "R3") (pin "2") (pinfunction "2_2") (pintype "passive"))
      (node (ref "SV1") (pin "P11") (pinfunction "11_P11") (pintype "passive"))
    )
    (net (code "54") (name "unconnected-(J1-4-PadP4)") (class "Default")
      (node (ref "J1") (pin "P4") (pinfunction "4_P4") (pintype "bidirectional"))
    )
    (net (code "55") (name "unconnected-(J1-6-PadP6)") (class "Default")
      (node (ref "J1") (pin "P6") (pinfunction "6_P6") (pintype "bidirectional"))
    )
    (net (code "56") (name "unconnected-(J4-SWO-Pad6)") (class "Default")
      (node (ref "J4") (pin "6") (pinfunction "SWO_6") (pintype "bidirectional"))
    )
    (net (code "57") (name "unconnected-(J4-~{RESET}-Pad3)") (class "Default")
      (node (ref "J4") (pin "3") (pinfunction "~{RESET}_3") (pintype "bidirectional"))
    )
    (net (code "58") (name "unconnected-(U4-P00{slash}AREF0-Pad4)") (class "Default")
      (node (ref "U4") (pin "4") (pinfunction "P00/AREF0_4") (pintype "bidirectional"))
    )
    (net (code "59") (name "unconnected-(U4-P01{slash}AIN2-Pad5)") (class "Default")
      (node (ref "U4") (pin "5") (pinfunction "P01/AIN2_5") (pintype "bidirectional"))
    )
    (net (code "60") (name "unconnected-(U4-P02{slash}AIN3-Pad6)") (class "Default")
      (node (ref "U4") (pin "6") (pinfunction "P02/AIN3_6") (pintype "bidirectional"))
    )
    (net (code "61") (name "unconnected-(U4-P03{slash}AIN4-Pad7)") (class "Default")
      (node (ref "U4") (pin "7") (pinfunction "P03/AIN4_7") (pintype "bidirectional"))
    )
    (net (code "62") (name "unconnected-(U4-P04{slash}AIN5-Pad8)") (class "Default")
      (node (ref "U4") (pin "8") (pinfunction "P04/AIN5_8") (pintype "bidirectional"))
    )
    (net (code "63") (name "unconnected-(U4-P06{slash}AIN7{slash}AREF1-Pad10)") (class "Default")
      (node (ref "U4") (pin "10") (pinfunction "P06/AIN7/AREF1_10") (pintype "bidirectional"))
    )
    (net (code "64") (name "unconnected-(U4-P07-Pad11)") (class "Default")
      (node (ref "U4") (pin "11") (pinfunction "P07_11") (pintype "bidirectional"))
    )
    (net (code "65") (name "unconnected-(U4-P08-Pad14)") (class "Default")
      (node (ref "U4") (pin "14") (pinfunction "P08_14") (pintype "bidirectional"))
    )
    (net (code "66") (name "unconnected-(U4-P09-Pad15)") (class "Default")
      (node (ref "U4") (pin "15") (pinfunction "P09_15") (pintype "bidirectional"))
    )
    (net (code "67") (name "unconnected-(U4-P10-Pad16)") (class "Default")
      (node (ref "U4") (pin "16") (pinfunction "P10_16") (pintype "bidirectional"))
    )
    (net (code "68") (name "unconnected-(U4-P11-Pad17)") (class "Default")
      (node (ref "U4") (pin "17") (pinfunction "P11_17") (pintype "bidirectional"))
    )
    (net (code "69") (name "unconnected-(U4-P12-Pad18)") (class "Default")
      (node (ref "U4") (pin "18") (pinfunction "P12_18") (pintype "bidirectional"))
    )
    (net (code "70") (name "unconnected-(U4-P13-Pad19)") (class "Default")
      (node (ref "U4") (pin "19") (pinfunction "P13_19") (pintype "bidirectional"))
    )
    (net (code "71") (name "unconnected-(U4-P14-Pad20)") (class "Default")
      (node (ref "U4") (pin "20") (pinfunction "P14_20") (pintype "bidirectional"))
    )
    (net (code "72") (name "unconnected-(U4-P15-Pad21)") (class "Default")
      (node (ref "U4") (pin "21") (pinfunction "P15_21") (pintype "bidirectional"))
    )
    (net (code "73") (name "unconnected-(U4-P16-Pad22)") (class "Default")
      (node (ref "U4") (pin "22") (pinfunction "P16_22") (pintype "bidirectional"))
    )
    (net (code "74") (name "unconnected-(U4-P17-Pad25)") (class "Default")
      (node (ref "U4") (pin "25") (pinfunction "P17_25") (pintype "bidirectional"))
    )
    (net (code "75") (name "unconnected-(U4-P18-Pad26)") (class "Default")
      (node (ref "U4") (pin "26") (pinfunction "P18_26") (pintype "bidirectional"))
    )
    (net (code "76") (name "unconnected-(U4-P19-Pad27)") (class "Default")
      (node (ref "U4") (pin "27") (pinfunction "P19_27") (pintype "bidirectional"))
    )
    (net (code "77") (name "unconnected-(U4-P20-Pad28)") (class "Default")
      (node (ref "U4") (pin "28") (pinfunction "P20_28") (pintype "bidirectional"))
    )
    (net (code "78") (name "unconnected-(U4-P21-Pad40)") (class "Default")
      (node (ref "U4") (pin "40") (pinfunction "P21_40") (pintype "bidirectional"))
    )
    (net (code "79") (name "unconnected-(U4-P22-Pad41)") (class "Default")
      (node (ref "U4") (pin "41") (pinfunction "P22_41") (pintype "bidirectional"))
    )
    (net (code "80") (name "unconnected-(U4-P23-Pad42)") (class "Default")
      (node (ref "U4") (pin "42") (pinfunction "P23_42") (pintype "bidirectional"))
    )
    (net (code "81") (name "unconnected-(U4-P24-Pad43)") (class "Default")
      (node (ref "U4") (pin "43") (pinfunction "P24_43") (pintype "bidirectional"))
    )
    (net (code "82") (name "unconnected-(U4-P25-Pad44)") (class "Default")
      (node (ref "U4") (pin "44") (pinfunction "P25_44") (pintype "bidirectional"))
    )
    (net (code "83") (name "unconnected-(U4-P26{slash}AIN0{slash}XL2-Pad45)") (class "Default")
      (node (ref "U4") (pin "45") (pinfunction "P26/AIN0/XL2_45") (pintype "bidirectional"))
    )
    (net (code "84") (name "unconnected-(U4-P30-Pad3)") (class "Default")
      (node (ref "U4") (pin "3") (pinfunction "P30_3") (pintype "bidirectional"))
    )
  )
)
